# lab4_analog_input.net
KiCad netlist of a schematic drawn in Altium Designer
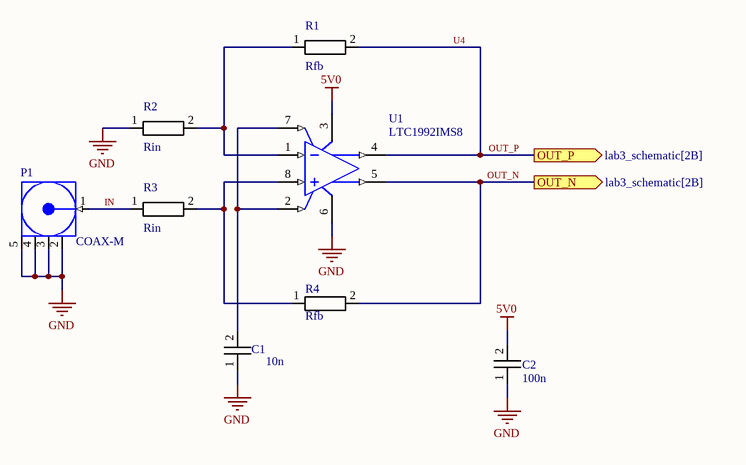
[diagram p0: lab4_analog_input.SchDoc]

(export (version "E")
  (design (tool "Eeschema 10.0.6"))
  (components
    (comp (ref "C1")
      (value "10n")
      (footprint "PcbLib_MW:0805_STD")
      (libsource (lib "Schlib_MW") (part "Capacitor"))
    )
    (comp (ref "C2")
      (value "100n")
      (footprint "PcbLib_MW:0805_STD")
      (libsource (lib "Schlib_MW") (part "Capacitor"))
    )
    (comp (ref "P1")
      (value "COAX-M")
      (footprint "MMCX2.54-V5")
      (description "RF Coaxial PCB Connector, MMCX; Thru-Hole, Vertical Mount Plug,  50 Ohm Impedance")
      (fields (field (name "PUBLISHER") "Altium Limited"))
      (libsource (lib "Miscellaneous Connectors") (part "COAX-M"))
    )
    (comp (ref "R1")
      (value "Rfb")
      (footprint "PcbLib_MW:0603")
      (libsource (lib "Schlib_MW") (part "Resistor"))
    )
    (comp (ref "R2")
      (value "Rin")
      (footprint "PcbLib_MW:0603")
      (libsource (lib "Schlib_MW") (part "Resistor"))
    )
    (comp (ref "R3")
      (value "Rin")
      (footprint "PcbLib_MW:0603")
      (libsource (lib "Schlib_MW") (part "Resistor"))
    )
    (comp (ref "R4")
      (value "Rfb")
      (footprint "PcbLib_MW:0603")
      (libsource (lib "Schlib_MW") (part "Resistor"))
    )
    (comp (ref "U1")
      (value "LTC1992IMS8")
      (footprint "PcbLib_MW:LT-MS8-8_L")
      (fields
        (field (name "LINEAR TECHNOLOGY PART NUMBER") "LTC1992")
        (field (name "MANUFACTURER") "Linear Technology")
      )
      (libsource (lib "Schlib_MW") (part "CMP-0359-00506-2"))
    )
  )
  (nets
    (net (code "1") (name "/IN") (class "Default")
      (node (ref "P1") (pin "1") (pinfunction "Signal_1") (pintype "input"))
      (node (ref "R3") (pin "1") (pinfunction "PIN_1") (pintype "passive"))
    )
    (net (code "2") (name "/OUT_N") (class "Default")
      (node (ref "R4") (pin "2") (pinfunction "PIN_2") (pintype "passive"))
      (node (ref "U1") (pin "5") (pinfunction "-OUT_5") (pintype "output"))
    )
    (net (code "3") (name "/OUT_P") (class "Default")
      (node (ref "R1") (pin "2") (pinfunction "PIN_2") (pintype "passive"))
      (node (ref "U1") (pin "4") (pinfunction "+OUT_4") (pintype "output"))
    )
    (net (code "4") (name "5V0") (class "Default")
      (node (ref "C2") (pin "2") (pinfunction "PIN_2") (pintype "passive"))
      (node (ref "U1") (pin "3") (pinfunction "+VS_3") (pintype "power_in"))
    )
    (net (code "5") (name "GND") (class "Default")
      (node (ref "C1") (pin "1") (pinfunction "PIN_1") (pintype "passive"))
      (node (ref "C2") (pin "1") (pinfunction "PIN_1") (pintype "passive"))
      (node (ref "P1") (pin "2") (pinfunction "GND_2") (pintype "power_in"))
      (node (ref "P1") (pin "3") (pinfunction "GND_3") (pintype "power_in"))
      (node (ref "P1") (pin "4") (pinfunction "GND_4") (pintype "power_in"))
      (node (ref "P1") (pin "5") (pinfunction "GND_5") (pintype "power_in"))
      (node (ref "R2") (pin "1") (pinfunction "PIN_1") (pintype "passive"))
      (node (ref "U1") (pin "6") (pinfunction "-VS_6") (pintype "power_in"))
    )
    (net (code "6") (name "Net-(U1-+IN)") (class "Default")
      (node (ref "R3") (pin "2") (pinfunction "PIN_2") (pintype "passive"))
      (node (ref "R4") (pin "1") (pinfunction "PIN_1") (pintype "passive"))
      (node (ref "U1") (pin "8") (pinfunction "+IN_8") (pintype "input"))
    )
    (net (code "7") (name "Net-(U1--IN)") (class "Default")
      (node (ref "R1") (pin "1") (pinfunction "PIN_1") (pintype "passive"))
      (node (ref "R2") (pin "2") (pinfunction "PIN_2") (pintype "passive"))
      (node (ref "U1") (pin "1") (pinfunction "-IN_1") (pintype "input"))
    )
    (net (code "8") (name "Net-(U1-VMID)") (class "Default")
      (node (ref "C1") (pin "2") (pinfunction "PIN_2") (pintype "passive"))
      (node (ref "U1") (pin "2") (pinfunction "VOCM_2") (pintype "input"))
      (node (ref "U1") (pin "7") (pinfunction "VMID_7") (pintype "input"))
    )
  )
)
